# Buzzer.net
KiCad netlist of a schematic drawn in Altium Designer
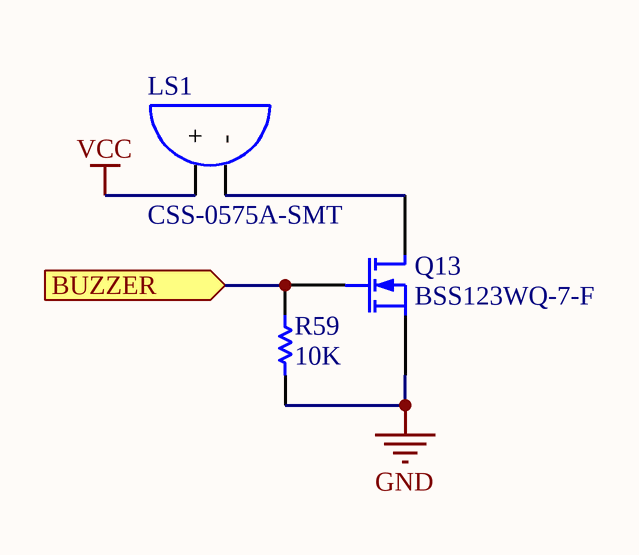
[diagram p0: Buzzer.SchDoc]

(export (version "E")
  (design (tool "Eeschema 10.0.6"))
  (components
    (comp (ref "LS1")
      (value "CSS-0575A-SMT")
      (footprint "CSS-0575A-SMT")
      (description "Magnetic Buzzer Transducer")
      (fields (field (name "MANUFACTURER") "CUI, Inc."))
      (libsource (lib "Components") (part "CSS-0575A-SMT"))
    )
    (comp (ref "Q13")
      (value "BSS123WQ-7-F")
      (footprint "SOT323-3")
      (description "N-Channel MOSFET")
      (fields (field (name "MANUFACTURER") "Diodes Incorporated"))
      (libsource (lib "MOSFETs") (part "BSS123WQ-7-F"))
    )
    (comp (ref "R59")
      (value "10K")
      (footprint "R0603[1608]")
      (description "10K 0.25W 1% 0603 (1005 Metric)")
      (fields (field (name "MANUFACTURER") "Vishay / Dale") (field (name "PARTNUMBER") "CRCW060310K0FKEAHP"))
      (libsource (lib "Resistors") (part "RES_10K_0603_1%"))
    )
  )
  (nets
    (net (code "1") (name "/BUZZER") (class "Default")
      (node (ref "Q13") (pin "1") (pinfunction "G_1") (pintype "passive"))
      (node (ref "R59") (pin "2") (pinfunction "2_2") (pintype "passive"))
    )
    (net (code "2") (name "GND") (class "Default")
      (node (ref "Q13") (pin "2") (pinfunction "S_2") (pintype "passive"))
      (node (ref "R59") (pin "1") (pinfunction "1_1") (pintype "passive"))
    )
    (net (code "3") (name "Net-(LS1--)") (class "Default")
      (node (ref "LS1") (pin "2") (pinfunction "-_2") (pintype "passive"))
      (node (ref "Q13") (pin "3") (pinfunction "D_3") (pintype "passive"))
    )
    (net (code "4") (name "VCC") (class "Default")
      (node (ref "LS1") (pin "1") (pinfunction "+_1") (pintype "passive"))
    )
  )
)
